# QCopterMV_LED_Sch.net
KiCad netlist of a schematic drawn in Altium Designer
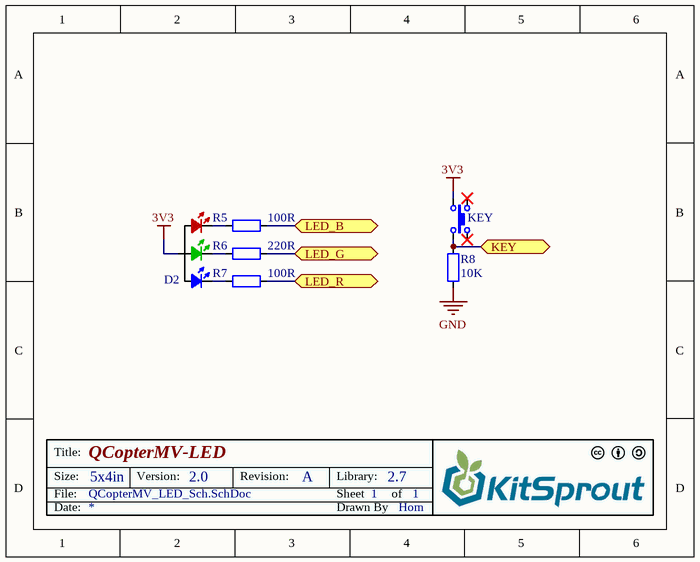
[diagram p0: QCopterMV_LED_Sch.SchDoc]

(export (version "E")
  (design (tool "Eeschema 10.0.6"))
  (components
    (comp (ref "D2")
      (value "LED_3528_RGB")
      (footprint "PCB_ActiveLED:LED_3528_RGB")
      (description "LED")
      (libsource (lib "SCH_Active") (part "LED_3528_RGB"))
    )
    (comp (ref "KEY")
      (value "ButtonTACT")
      (footprint "PCB_Switch:ButtonTACT_3.5*3.55_90")
      (description "Button")
      (libsource (lib "SCH_Switch") (part "ButtonTACT"))
    )
    (comp (ref "R5")
      (value "100R")
      (footprint "PCB_PassiveRes:RES_0603")
      (description "Resistor")
      (fields (field (name "Comment") "Res_0603"))
      (libsource (lib "SCH_Passive") (part "Res_0603"))
    )
    (comp (ref "R6")
      (value "220R")
      (footprint "PCB_PassiveRes:RES_0603")
      (description "Resistor")
      (fields (field (name "Comment") "Res_0603"))
      (libsource (lib "SCH_Passive") (part "Res_0603"))
    )
    (comp (ref "R7")
      (value "100R")
      (footprint "PCB_PassiveRes:RES_0603")
      (description "Resistor")
      (fields (field (name "Comment") "Res_0603"))
      (libsource (lib "SCH_Passive") (part "Res_0603"))
    )
    (comp (ref "R8")
      (value "10K")
      (footprint "PCB_PassiveRes:RES_0603")
      (description "Resistor")
      (fields (field (name "Comment") "Res_0603"))
      (libsource (lib "") (part "Res_0603_1"))
    )
  )
  (nets
    (net (code "1") (name "/KEY") (class "Default")
      (node (ref "KEY") (pin "4") (pinfunction "4_4") (pintype "passive"))
      (node (ref "R8") (pin "2") (pinfunction "2_2") (pintype "passive"))
    )
    (net (code "2") (name "/LED_B") (class "Default")
      (node (ref "R5") (pin "2") (pinfunction "2_2") (pintype "passive"))
    )
    (net (code "3") (name "/LED_G") (class "Default")
      (node (ref "R6") (pin "2") (pinfunction "2_2") (pintype "passive"))
    )
    (net (code "4") (name "/LED_R") (class "Default")
      (node (ref "R7") (pin "2") (pinfunction "2_2") (pintype "passive"))
    )
    (net (code "5") (name "3V3") (class "Default")
      (node (ref "D2") (pin "2") (pinfunction "A_2") (pintype "passive"))
      (node (ref "KEY") (pin "3") (pinfunction "3_3") (pintype "passive"))
    )
    (net (code "6") (name "GND") (class "Default")
      (node (ref "R8") (pin "1") (pinfunction "1_1") (pintype "passive"))
    )
    (net (code "7") (name "Net-(D2-B)") (class "Default")
      (node (ref "D2") (pin "4") (pinfunction "B_4") (pintype "passive"))
      (node (ref "R7") (pin "1") (pinfunction "1_1") (pintype "passive"))
    )
    (net (code "8") (name "Net-(D2-G)") (class "Default")
      (node (ref "D2") (pin "3") (pinfunction "G_3") (pintype "passive"))
      (node (ref "R6") (pin "1") (pinfunction "1_1") (pintype "passive"))
    )
    (net (code "9") (name "Net-(D2-R)") (class "Default")
      (node (ref "D2") (pin "1") (pinfunction "R_1") (pintype "passive"))
      (node (ref "R5") (pin "1") (pinfunction "1_1") (pintype "passive"))
    )
    (net (code "10") (name "unconnected-(KEY-Pad1)") (class "Default")
      (node (ref "KEY") (pin "1") (pinfunction "1_1") (pintype "passive+no_connect"))
    )
    (net (code "11") (name "unconnected-(KEY-Pad2)") (class "Default")
      (node (ref "KEY") (pin "2") (pinfunction "2_2") (pintype "passive+no_connect"))
    )
  )
)
